# 09_MeasInUI.net
KiCad netlist of a schematic drawn in Altium Designer
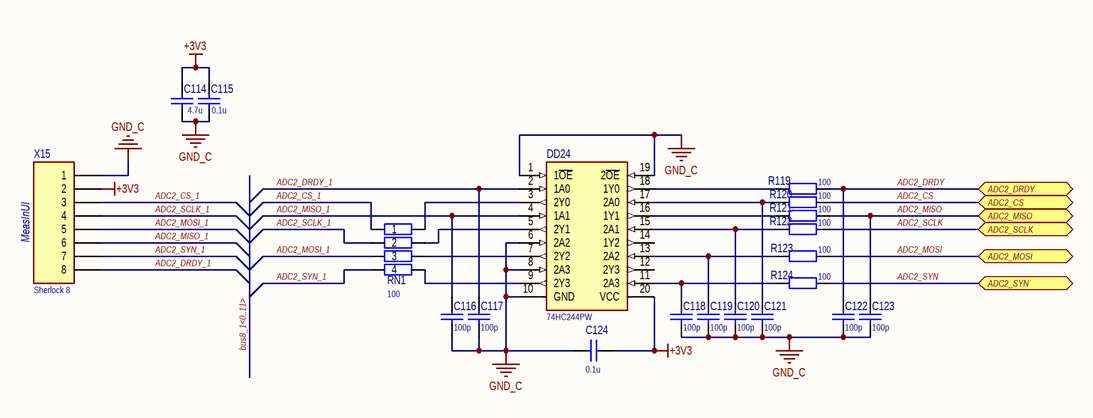
[diagram p0: 09_MeasInUI.SchDoc]

(export (version "E")
  (design (tool "Eeschema 10.0.6"))
  (components
    (comp (ref "C114")
      (value "4.7u")
      (footprint "mainLib:SMD_C_0805")
      (description "SMD C 0805 MURATA 50V 5% NP0")
      (fields (field (name "PARTNUMBER") "GRM21BR61E475M") (field (name "MANUFACTURER") "MURATA"))
      (libsource (lib "mainRCLib") (part "C0805 4.7u 25V 20%  X5R"))
    )
    (comp (ref "C115")
      (value "0.1u")
      (footprint "mainLib:SMD_C_0603")
      (description "SMD C 0603 MURATA 50V 10% X7R")
      (fields (field (name "PARTNUMBER") "GRM188R71H104K") (field (name "MANUFACTURER") "MURATA"))
      (libsource (lib "mainRCLib") (part "C0603 0.1u 50V 10%"))
    )
    (comp (ref "C116")
      (value "100p")
      (footprint "mainLib:SMD_C_0603")
      (description "SMD C 0603 MURATA 100V 5% NP0")
      (fields (field (name "PARTNUMBER") "GRM1885C2A101JA01") (field (name "MANUFACTURER") "MURATA"))
      (libsource (lib "mainRCLib") (part "C0603 100p 100V 5%"))
    )
    (comp (ref "C117")
      (value "100p")
      (footprint "mainLib:SMD_C_0603")
      (description "SMD C 0603 MURATA 100V 5% NP0")
      (fields (field (name "PARTNUMBER") "GRM1885C2A101JA01") (field (name "MANUFACTURER") "MURATA"))
      (libsource (lib "mainRCLib") (part "C0603 100p 100V 5%"))
    )
    (comp (ref "C118")
      (value "100p")
      (footprint "mainLib:SMD_C_0603")
      (description "SMD C 0603 MURATA 100V 5% NP0")
      (fields (field (name "PARTNUMBER") "GRM1885C2A101JA01") (field (name "MANUFACTURER") "MURATA"))
      (libsource (lib "mainRCLib") (part "C0603 100p 100V 5%"))
    )
    (comp (ref "C119")
      (value "100p")
      (footprint "mainLib:SMD_C_0603")
      (description "SMD C 0603 MURATA 100V 5% NP0")
      (fields (field (name "PARTNUMBER") "GRM1885C2A101JA01") (field (name "MANUFACTURER") "MURATA"))
      (libsource (lib "mainRCLib") (part "C0603 100p 100V 5%"))
    )
    (comp (ref "C120")
      (value "100p")
      (footprint "mainLib:SMD_C_0603")
      (description "SMD C 0603 MURATA 100V 5% NP0")
      (fields (field (name "PARTNUMBER") "GRM1885C2A101JA01") (field (name "MANUFACTURER") "MURATA"))
      (libsource (lib "mainRCLib") (part "C0603 100p 100V 5%"))
    )
    (comp (ref "C121")
      (value "100p")
      (footprint "mainLib:SMD_C_0603")
      (description "SMD C 0603 MURATA 100V 5% NP0")
      (fields (field (name "PARTNUMBER") "GRM1885C2A101JA01") (field (name "MANUFACTURER") "MURATA"))
      (libsource (lib "mainRCLib") (part "C0603 100p 100V 5%"))
    )
    (comp (ref "C122")
      (value "100p")
      (footprint "mainLib:SMD_C_0603")
      (description "SMD C 0603 MURATA 100V 5% NP0")
      (fields (field (name "PARTNUMBER") "GRM1885C2A101JA01") (field (name "MANUFACTURER") "MURATA"))
      (libsource (lib "mainRCLib") (part "C0603 100p 100V 5%"))
    )
    (comp (ref "C123")
      (value "100p")
      (footprint "mainLib:SMD_C_0603")
      (description "SMD C 0603 MURATA 100V 5% NP0")
      (fields (field (name "PARTNUMBER") "GRM1885C2A101JA01") (field (name "MANUFACTURER") "MURATA"))
      (libsource (lib "mainRCLib") (part "C0603 100p 100V 5%"))
    )
    (comp (ref "C124")
      (value "0.1u")
      (footprint "mainLib:SMD_C_0603")
      (description "SMD C 0603 MURATA 50V 10% X7R")
      (fields (field (name "PARTNUMBER") "GRM188R71H104K") (field (name "MANUFACTURER") "MURATA"))
      (libsource (lib "mainRCLib") (part "C0603 0.1u 50V 10%"))
    )
    (comp (ref "DD24")
      (value "74HC244PW")
      (footprint "mainLib:TSSOP20")
      (description "Octal Buffer/Line Driver with 3-State Outputs, PW0020A")
      (fields (field (name "MANUFACTURER") "NXP"))
      (libsource (lib "mainLib") (part "74HC244PW"))
    )
    (comp (ref "R119")
      (value "100")
      (footprint "SMD_R_0603")
      (description "SMD R 0603 VISHAY 0.1W 75V 1% 100ppm")
      (fields (field (name "PARTNUMBER") "CRCW0603100RFK") (field (name "MANUFACTURER") "VISHAY"))
      (libsource (lib "mainRCLib") (part "R0603 100 1%"))
    )
    (comp (ref "R120")
      (value "100")
      (footprint "SMD_R_0603")
      (description "SMD R 0603 VISHAY 0.1W 75V 1% 100ppm")
      (fields (field (name "PARTNUMBER") "CRCW0603100RFK") (field (name "MANUFACTURER") "VISHAY"))
      (libsource (lib "mainRCLib") (part "R0603 100 1%"))
    )
    (comp (ref "R121")
      (value "100")
      (footprint "SMD_R_0603")
      (description "SMD R 0603 VISHAY 0.1W 75V 1% 100ppm")
      (fields (field (name "PARTNUMBER") "CRCW0603100RFK") (field (name "MANUFACTURER") "VISHAY"))
      (libsource (lib "mainRCLib") (part "R0603 100 1%"))
    )
    (comp (ref "R122")
      (value "100")
      (footprint "SMD_R_0603")
      (description "SMD R 0603 VISHAY 0.1W 75V 1% 100ppm")
      (fields (field (name "PARTNUMBER") "CRCW0603100RFK") (field (name "MANUFACTURER") "VISHAY"))
      (libsource (lib "mainRCLib") (part "R0603 100 1%"))
    )
    (comp (ref "R123")
      (value "100")
      (footprint "SMD_R_0603")
      (description "SMD R 0603 VISHAY 0.1W 75V 1% 100ppm")
      (fields (field (name "PARTNUMBER") "CRCW0603100RFK") (field (name "MANUFACTURER") "VISHAY"))
      (libsource (lib "mainRCLib") (part "R0603 100 1%"))
    )
    (comp (ref "R124")
      (value "100")
      (footprint "SMD_R_0603")
      (description "SMD R 0603 VISHAY 0.1W 75V 1% 100ppm")
      (fields (field (name "PARTNUMBER") "CRCW0603100RFK") (field (name "MANUFACTURER") "VISHAY"))
      (libsource (lib "mainRCLib") (part "R0603 100 1%"))
    )
    (comp (ref "RN1")
      (value "100")
      (footprint "mainLib:CRA06S")
      (description "SMD RESISTOR ARRAY VISHAY 0.063W 50V 1% 100ppm")
      (fields (field (name "PARTNUMBER") "CRA06S083100RF") (field (name "MANUFACTURER") "VISHAY"))
      (libsource (lib "mainRCLib") (part "CRA06S 4x100 1%"))
    )
    (comp (ref "X15")
      (value "Sherlock 8")
      (footprint "mainLib:35362-0850")
      (description "Sherlock 8 Side, 2A 125V 2mm")
      (fields (field (name "PARTNUMBER") "35362-0850") (field (name "MANUFACTURER") "MOLEX"))
      (libsource (lib "mainLib") (part "35362-0850"))
    )
  )
  (nets
    (net (code "2") (name "+3V3") (class "Default")
      (node (ref "C114") (pin "2") (pinfunction "2_2") (pintype "passive"))
      (node (ref "C115") (pin "2") (pinfunction "2_2") (pintype "passive"))
      (node (ref "C124") (pin "2") (pinfunction "2_2") (pintype "passive"))
      (node (ref "DD24") (pin "20") (pinfunction "VCC_20") (pintype "power_in"))
      (node (ref "X15") (pin "2") (pinfunction "2_2") (pintype "passive"))
    )
    (net (code "3") (name "/ADC2_CS") (class "Default")
      (node (ref "R120") (pin "2") (pinfunction "2_2") (pintype "passive"))
    )
    (net (code "4") (name "/ADC2_CS_1") (class "Default")
      (node (ref "RN1") (pin "1") (pinfunction "1_1") (pintype "passive"))
      (node (ref "X15") (pin "3") (pinfunction "3_3") (pintype "passive"))
    )
    (net (code "5") (name "/ADC2_DRDY") (class "Default")
      (node (ref "C122") (pin "1") (pinfunction "1_1") (pintype "passive"))
      (node (ref "R119") (pin "2") (pinfunction "2_2") (pintype "passive"))
    )
    (net (code "6") (name "/ADC2_DRDY_1") (class "Default")
      (node (ref "C117") (pin "1") (pinfunction "1_1") (pintype "passive"))
      (node (ref "DD24") (pin "2") (pinfunction "1A0_2") (pintype "input"))
      (node (ref "X15") (pin "8") (pinfunction "8_8") (pintype "passive"))
    )
    (net (code "7") (name "/ADC2_MISO") (class "Default")
      (node (ref "C123") (pin "1") (pinfunction "1_1") (pintype "passive"))
      (node (ref "R121") (pin "2") (pinfunction "2_2") (pintype "passive"))
    )
    (net (code "8") (name "/ADC2_MISO_1") (class "Default")
      (node (ref "C116") (pin "1") (pinfunction "1_1") (pintype "passive"))
      (node (ref "DD24") (pin "4") (pinfunction "1A1_4") (pintype "input"))
      (node (ref "X15") (pin "6") (pinfunction "6_6") (pintype "passive"))
    )
    (net (code "9") (name "/ADC2_MOSI") (class "Default")
      (node (ref "R123") (pin "2") (pinfunction "2_2") (pintype "passive"))
    )
    (net (code "10") (name "/ADC2_MOSI_1") (class "Default")
      (node (ref "RN1") (pin "3") (pinfunction "3_3") (pintype "passive"))
      (node (ref "X15") (pin "5") (pinfunction "5_5") (pintype "passive"))
    )
    (net (code "11") (name "/ADC2_SCLK") (class "Default")
      (node (ref "R122") (pin "2") (pinfunction "2_2") (pintype "passive"))
    )
    (net (code "12") (name "/ADC2_SCLK_1") (class "Default")
      (node (ref "RN1") (pin "2") (pinfunction "2_2") (pintype "passive"))
      (node (ref "X15") (pin "4") (pinfunction "4_4") (pintype "passive"))
    )
    (net (code "13") (name "/ADC2_SYN") (class "Default")
      (node (ref "R124") (pin "2") (pinfunction "2_2") (pintype "passive"))
    )
    (net (code "14") (name "/ADC2_SYN_1") (class "Default")
      (node (ref "RN1") (pin "4") (pinfunction "4_4") (pintype "passive"))
      (node (ref "X15") (pin "7") (pinfunction "7_7") (pintype "passive"))
    )
    (net (code "16") (name "GND_C") (class "Default")
      (node (ref "C114") (pin "1") (pinfunction "1_1") (pintype "passive"))
      (node (ref "C115") (pin "1") (pinfunction "1_1") (pintype "passive"))
      (node (ref "C116") (pin "2") (pinfunction "2_2") (pintype "passive"))
      (node (ref "C117") (pin "2") (pinfunction "2_2") (pintype "passive"))
      (node (ref "C118") (pin "2") (pinfunction "2_2") (pintype "passive"))
      (node (ref "C119") (pin "2") (pinfunction "2_2") (pintype "passive"))
      (node (ref "C120") (pin "2") (pinfunction "2_2") (pintype "passive"))
      (node (ref "C121") (pin "2") (pinfunction "2_2") (pintype "passive"))
      (node (ref "C122") (pin "2") (pinfunction "2_2") (pintype "passive"))
      (node (ref "C123") (pin "2") (pinfunction "2_2") (pintype "passive"))
      (node (ref "C124") (pin "1") (pinfunction "1_1") (pintype "passive"))
      (node (ref "DD24") (pin "1") (pinfunction "1~{OE}_1") (pintype "input"))
      (node (ref "DD24") (pin "10") (pinfunction "GND_10") (pintype "power_in"))
      (node (ref "DD24") (pin "19") (pinfunction "2~{OE}_19") (pintype "input"))
      (node (ref "DD24") (pin "6") (pinfunction "2A2_6") (pintype "input"))
      (node (ref "DD24") (pin "8") (pinfunction "2A3_8") (pintype "input"))
      (node (ref "X15") (pin "1") (pinfunction "1_1") (pintype "passive"))
    )
    (net (code "17") (name "Net-(C118-Pad1)") (class "Default")
      (node (ref "C118") (pin "1") (pinfunction "1_1") (pintype "passive"))
      (node (ref "DD24") (pin "11") (pinfunction "2A3_11") (pintype "input"))
      (node (ref "R124") (pin "1") (pinfunction "1_1") (pintype "passive"))
    )
    (net (code "18") (name "Net-(C119-Pad1)") (class "Default")
      (node (ref "C119") (pin "1") (pinfunction "1_1") (pintype "passive"))
      (node (ref "DD24") (pin "13") (pinfunction "2A2_13") (pintype "input"))
      (node (ref "R123") (pin "1") (pinfunction "1_1") (pintype "passive"))
    )
    (net (code "19") (name "Net-(DD24-1Y0)") (class "Default")
      (node (ref "DD24") (pin "18") (pinfunction "1Y0_18") (pintype "output"))
      (node (ref "R119") (pin "1") (pinfunction "1_1") (pintype "passive"))
    )
    (net (code "20") (name "Net-(DD24-1Y1)") (class "Default")
      (node (ref "DD24") (pin "16") (pinfunction "1Y1_16") (pintype "output"))
      (node (ref "R121") (pin "1") (pinfunction "1_1") (pintype "passive"))
    )
    (net (code "21") (name "Net-(DD24-2A0)") (class "Default")
      (node (ref "C121") (pin "1") (pinfunction "1_1") (pintype "passive"))
      (node (ref "DD24") (pin "17") (pinfunction "2A0_17") (pintype "input"))
      (node (ref "R120") (pin "1") (pinfunction "1_1") (pintype "passive"))
    )
    (net (code "22") (name "Net-(DD24-2A1)") (class "Default")
      (node (ref "C120") (pin "1") (pinfunction "1_1") (pintype "passive"))
      (node (ref "DD24") (pin "15") (pinfunction "2A1_15") (pintype "input"))
      (node (ref "R122") (pin "1") (pinfunction "1_1") (pintype "passive"))
    )
    (net (code "23") (name "Net-(DD24-2Y0)") (class "Default")
      (node (ref "DD24") (pin "3") (pinfunction "2Y0_3") (pintype "output"))
      (node (ref "RN1") (pin "8") (pinfunction "8_8") (pintype "passive"))
    )
    (net (code "24") (name "Net-(DD24-2Y1)") (class "Default")
      (node (ref "DD24") (pin "5") (pinfunction "2Y1_5") (pintype "output"))
      (node (ref "RN1") (pin "7") (pinfunction "7_7") (pintype "passive"))
    )
    (net (code "25") (name "Net-(DD24-2Y2)") (class "Default")
      (node (ref "DD24") (pin "7") (pinfunction "2Y2_7") (pintype "output"))
      (node (ref "RN1") (pin "6") (pinfunction "6_6") (pintype "passive"))
    )
    (net (code "26") (name "Net-(DD24-2Y3-Pad9)") (class "Default")
      (node (ref "DD24") (pin "9") (pinfunction "2Y3_9") (pintype "output"))
      (node (ref "RN1") (pin "5") (pinfunction "5_5") (pintype "passive"))
    )
    (net (code "27") (name "unconnected-(DD24-1Y2-Pad14)") (class "Default")
      (node (ref "DD24") (pin "14") (pinfunction "1Y2_14") (pintype "output"))
    )
    (net (code "28") (name "unconnected-(DD24-2Y3-Pad12)") (class "Default")
      (node (ref "DD24") (pin "12") (pinfunction "2Y3_12") (pintype "output"))
    )
  )
)
